# lab4.net
KiCad netlist of a schematic drawn in Altium Designer
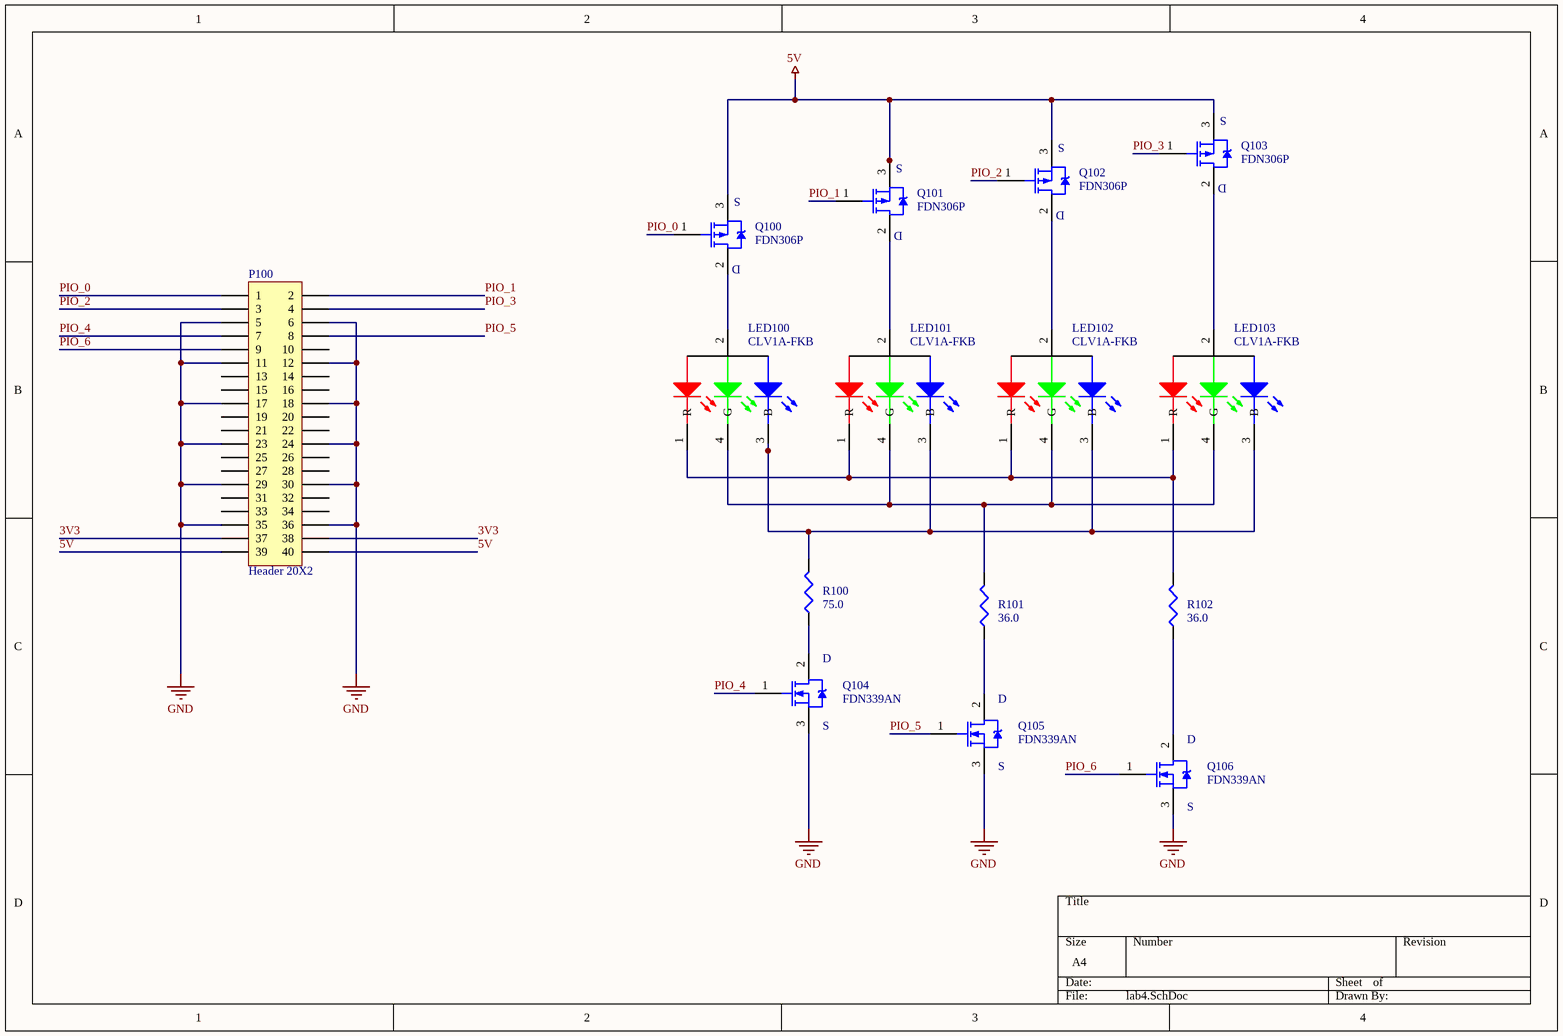
[diagram p0: lab4.SchDoc]

(export (version "E")
  (design (tool "Eeschema 10.0.6"))
  (components
    (comp (ref "LED100")
      (value "CLV1A-FKB")
      (footprint "PLCC4")
      (libsource (lib "My_LED") (part "CLV1A-FKB"))
    )
    (comp (ref "LED101")
      (value "CLV1A-FKB")
      (footprint "PLCC4")
      (libsource (lib "My_LED") (part "CLV1A-FKB"))
    )
    (comp (ref "LED102")
      (value "CLV1A-FKB")
      (footprint "PLCC4")
      (libsource (lib "My_LED") (part "CLV1A-FKB"))
    )
    (comp (ref "LED103")
      (value "CLV1A-FKB")
      (footprint "PLCC4")
      (libsource (lib "My_LED") (part "CLV1A-FKB"))
    )
    (comp (ref "P100")
      (value "Header 20X2")
      (footprint "HDR2X20")
      (description "Header, 20-Pin, Dual row")
      (fields (field (name "PUBLISHER") "Altium Limited"))
      (libsource (lib "Miscellaneous Connectors") (part "Header 20X2"))
    )
    (comp (ref "Q100")
      (value "FDN306P")
      (footprint "SOT23_M:SOT23-3M")
      (description "Pch MOSFET")
      (libsource (lib "MY_Fairchild_MOSFETS") (part "FDN304P"))
    )
    (comp (ref "Q101")
      (value "FDN306P")
      (footprint "SOT23_M:SOT23-3M")
      (description "Pch MOSFET")
      (libsource (lib "MY_Fairchild_MOSFETS") (part "FDN304P"))
    )
    (comp (ref "Q102")
      (value "FDN306P")
      (footprint "SOT23_M:SOT23-3M")
      (description "Pch MOSFET")
      (libsource (lib "MY_Fairchild_MOSFETS") (part "FDN304P"))
    )
    (comp (ref "Q103")
      (value "FDN306P")
      (footprint "SOT23_M:SOT23-3M")
      (description "Pch MOSFET")
      (libsource (lib "MY_Fairchild_MOSFETS") (part "FDN304P"))
    )
    (comp (ref "Q104")
      (value "FDN339AN")
      (footprint "SOT23_M:SOT23-3M")
      (description "Nch MOSFET")
      (libsource (lib "MY_Fairchild_MOSFETS") (part "FDN339AN"))
    )
    (comp (ref "Q105")
      (value "FDN339AN")
      (footprint "SOT23_M:SOT23-3M")
      (description "Nch MOSFET")
      (libsource (lib "MY_Fairchild_MOSFETS") (part "FDN339AN"))
    )
    (comp (ref "Q106")
      (value "FDN339AN")
      (footprint "SOT23_M:SOT23-3M")
      (description "Nch MOSFET")
      (libsource (lib "MY_Fairchild_MOSFETS") (part "FDN339AN"))
    )
    (comp (ref "R100")
      (value "75.0")
      (footprint "RESC2012M")
      (description "Resistor")
      (fields (field (name "Comment") "Res3") (field (name "PUBLISHER") "Altium Limited"))
      (libsource (lib "My_Miscellaneous Devices") (part "Res3"))
    )
    (comp (ref "R101")
      (value "36.0")
      (footprint "RESC2012M")
      (description "Resistor")
      (fields (field (name "Comment") "Res3") (field (name "PUBLISHER") "Altium Limited"))
      (libsource (lib "My_Miscellaneous Devices") (part "Res3"))
    )
    (comp (ref "R102")
      (value "36.0")
      (footprint "RESC2012M")
      (description "Resistor")
      (fields (field (name "Comment") "Res3") (field (name "PUBLISHER") "Altium Limited"))
      (libsource (lib "My_Miscellaneous Devices") (part "Res3"))
    )
  )
  (nets
    (net (code "1") (name "/3V3") (class "Default")
      (node (ref "P100") (pin "37") (pinfunction "37_37") (pintype "passive"))
      (node (ref "P100") (pin "38") (pinfunction "38_38") (pintype "passive"))
    )
    (net (code "2") (name "/PIO_0") (class "Default")
      (node (ref "P100") (pin "1") (pinfunction "1_1") (pintype "passive"))
      (node (ref "Q100") (pin "1") (pinfunction "G_1") (pintype "passive"))
    )
    (net (code "3") (name "/PIO_1") (class "Default")
      (node (ref "P100") (pin "2") (pinfunction "2_2") (pintype "passive"))
      (node (ref "Q101") (pin "1") (pinfunction "G_1") (pintype "passive"))
    )
    (net (code "4") (name "/PIO_2") (class "Default")
      (node (ref "P100") (pin "3") (pinfunction "3_3") (pintype "passive"))
      (node (ref "Q102") (pin "1") (pinfunction "G_1") (pintype "passive"))
    )
    (net (code "5") (name "/PIO_3") (class "Default")
      (node (ref "P100") (pin "4") (pinfunction "4_4") (pintype "passive"))
      (node (ref "Q103") (pin "1") (pinfunction "G_1") (pintype "passive"))
    )
    (net (code "6") (name "/PIO_4") (class "Default")
      (node (ref "P100") (pin "7") (pinfunction "7_7") (pintype "passive"))
      (node (ref "Q104") (pin "1") (pinfunction "G_1") (pintype "passive"))
    )
    (net (code "7") (name "/PIO_5") (class "Default")
      (node (ref "P100") (pin "8") (pinfunction "8_8") (pintype "passive"))
      (node (ref "Q105") (pin "1") (pinfunction "G_1") (pintype "passive"))
    )
    (net (code "8") (name "/PIO_6") (class "Default")
      (node (ref "P100") (pin "9") (pinfunction "9_9") (pintype "passive"))
      (node (ref "Q106") (pin "1") (pinfunction "G_1") (pintype "passive"))
    )
    (net (code "9") (name "5V") (class "Default")
      (node (ref "P100") (pin "39") (pinfunction "39_39") (pintype "passive"))
      (node (ref "P100") (pin "40") (pinfunction "40_40") (pintype "passive"))
      (node (ref "Q100") (pin "3") (pinfunction "S_3") (pintype "passive"))
      (node (ref "Q101") (pin "3") (pinfunction "S_3") (pintype "passive"))
      (node (ref "Q102") (pin "3") (pinfunction "S_3") (pintype "passive"))
      (node (ref "Q103") (pin "3") (pinfunction "S_3") (pintype "passive"))
    )
    (net (code "10") (name "GND") (class "Default")
      (node (ref "P100") (pin "11") (pinfunction "11_11") (pintype "passive"))
      (node (ref "P100") (pin "12") (pinfunction "12_12") (pintype "passive"))
      (node (ref "P100") (pin "17") (pinfunction "17_17") (pintype "passive"))
      (node (ref "P100") (pin "18") (pinfunction "18_18") (pintype "passive"))
      (node (ref "P100") (pin "23") (pinfunction "23_23") (pintype "passive"))
      (node (ref "P100") (pin "24") (pinfunction "24_24") (pintype "passive"))
      (node (ref "P100") (pin "29") (pinfunction "29_29") (pintype "passive"))
      (node (ref "P100") (pin "30") (pinfunction "30_30") (pintype "passive"))
      (node (ref "P100") (pin "35") (pinfunction "35_35") (pintype "passive"))
      (node (ref "P100") (pin "36") (pinfunction "36_36") (pintype "passive"))
      (node (ref "P100") (pin "5") (pinfunction "5_5") (pintype "passive"))
      (node (ref "P100") (pin "6") (pinfunction "6_6") (pintype "passive"))
      (node (ref "Q104") (pin "3") (pinfunction "S_3") (pintype "passive"))
      (node (ref "Q105") (pin "3") (pinfunction "S_3") (pintype "passive"))
      (node (ref "Q106") (pin "3") (pinfunction "S_3") (pintype "passive"))
    )
    (net (code "11") (name "Net-(LED100-A)") (class "Default")
      (node (ref "LED100") (pin "2") (pinfunction "A_2") (pintype "passive"))
      (node (ref "Q100") (pin "2") (pinfunction "D_2") (pintype "passive"))
    )
    (net (code "12") (name "Net-(LED100-B)") (class "Default")
      (node (ref "LED100") (pin "3") (pinfunction "B_3") (pintype "passive"))
      (node (ref "LED101") (pin "3") (pinfunction "B_3") (pintype "passive"))
      (node (ref "LED102") (pin "3") (pinfunction "B_3") (pintype "passive"))
      (node (ref "LED103") (pin "3") (pinfunction "B_3") (pintype "passive"))
      (node (ref "R100") (pin "2") (pinfunction "2_2") (pintype "passive"))
    )
    (net (code "13") (name "Net-(LED100-G)") (class "Default")
      (node (ref "LED100") (pin "4") (pinfunction "G_4") (pintype "passive"))
      (node (ref "LED101") (pin "4") (pinfunction "G_4") (pintype "passive"))
      (node (ref "LED102") (pin "4") (pinfunction "G_4") (pintype "passive"))
      (node (ref "LED103") (pin "4") (pinfunction "G_4") (pintype "passive"))
      (node (ref "R101") (pin "2") (pinfunction "2_2") (pintype "passive"))
    )
    (net (code "14") (name "Net-(LED100-R)") (class "Default")
      (node (ref "LED100") (pin "1") (pinfunction "R_1") (pintype "passive"))
      (node (ref "LED101") (pin "1") (pinfunction "R_1") (pintype "passive"))
      (node (ref "LED102") (pin "1") (pinfunction "R_1") (pintype "passive"))
      (node (ref "LED103") (pin "1") (pinfunction "R_1") (pintype "passive"))
      (node (ref "R102") (pin "2") (pinfunction "2_2") (pintype "passive"))
    )
    (net (code "15") (name "Net-(LED101-A)") (class "Default")
      (node (ref "LED101") (pin "2") (pinfunction "A_2") (pintype "passive"))
      (node (ref "Q101") (pin "2") (pinfunction "D_2") (pintype "passive"))
    )
    (net (code "16") (name "Net-(LED102-A)") (class "Default")
      (node (ref "LED102") (pin "2") (pinfunction "A_2") (pintype "passive"))
      (node (ref "Q102") (pin "2") (pinfunction "D_2") (pintype "passive"))
    )
    (net (code "17") (name "Net-(LED103-A)") (class "Default")
      (node (ref "LED103") (pin "2") (pinfunction "A_2") (pintype "passive"))
      (node (ref "Q103") (pin "2") (pinfunction "D_2") (pintype "passive"))
    )
    (net (code "18") (name "Net-(Q104-D)") (class "Default")
      (node (ref "Q104") (pin "2") (pinfunction "D_2") (pintype "passive"))
      (node (ref "R100") (pin "1") (pinfunction "1_1") (pintype "passive"))
    )
    (net (code "19") (name "Net-(Q105-D)") (class "Default")
      (node (ref "Q105") (pin "2") (pinfunction "D_2") (pintype "passive"))
      (node (ref "R101") (pin "1") (pinfunction "1_1") (pintype "passive"))
    )
    (net (code "20") (name "Net-(Q106-D)") (class "Default")
      (node (ref "Q106") (pin "2") (pinfunction "D_2") (pintype "passive"))
      (node (ref "R102") (pin "1") (pinfunction "1_1") (pintype "passive"))
    )
    (net (code "21") (name "unconnected-(P100-Pad10)") (class "Default")
      (node (ref "P100") (pin "10") (pinfunction "10_10") (pintype "passive"))
    )
    (net (code "22") (name "unconnected-(P100-Pad13)") (class "Default")
      (node (ref "P100") (pin "13") (pinfunction "13_13") (pintype "passive"))
    )
    (net (code "23") (name "unconnected-(P100-Pad14)") (class "Default")
      (node (ref "P100") (pin "14") (pinfunction "14_14") (pintype "passive"))
    )
    (net (code "24") (name "unconnected-(P100-Pad15)") (class "Default")
      (node (ref "P100") (pin "15") (pinfunction "15_15") (pintype "passive"))
    )
    (net (code "25") (name "unconnected-(P100-Pad16)") (class "Default")
      (node (ref "P100") (pin "16") (pinfunction "16_16") (pintype "passive"))
    )
    (net (code "26") (name "unconnected-(P100-Pad19)") (class "Default")
      (node (ref "P100") (pin "19") (pinfunction "19_19") (pintype "passive"))
    )
    (net (code "27") (name "unconnected-(P100-Pad20)") (class "Default")
      (node (ref "P100") (pin "20") (pinfunction "20_20") (pintype "passive"))
    )
    (net (code "28") (name "unconnected-(P100-Pad21)") (class "Default")
      (node (ref "P100") (pin "21") (pinfunction "21_21") (pintype "passive"))
    )
    (net (code "29") (name "unconnected-(P100-Pad22)") (class "Default")
      (node (ref "P100") (pin "22") (pinfunction "22_22") (pintype "passive"))
    )
    (net (code "30") (name "unconnected-(P100-Pad25)") (class "Default")
      (node (ref "P100") (pin "25") (pinfunction "25_25") (pintype "passive"))
    )
    (net (code "31") (name "unconnected-(P100-Pad26)") (class "Default")
      (node (ref "P100") (pin "26") (pinfunction "26_26") (pintype "passive"))
    )
    (net (code "32") (name "unconnected-(P100-Pad27)") (class "Default")
      (node (ref "P100") (pin "27") (pinfunction "27_27") (pintype "passive"))
    )
    (net (code "33") (name "unconnected-(P100-Pad28)") (class "Default")
      (node (ref "P100") (pin "28") (pinfunction "28_28") (pintype "passive"))
    )
    (net (code "34") (name "unconnected-(P100-Pad31)") (class "Default")
      (node (ref "P100") (pin "31") (pinfunction "31_31") (pintype "passive"))
    )
    (net (code "35") (name "unconnected-(P100-Pad32)") (class "Default")
      (node (ref "P100") (pin "32") (pinfunction "32_32") (pintype "passive"))
    )
    (net (code "36") (name "unconnected-(P100-Pad33)") (class "Default")
      (node (ref "P100") (pin "33") (pinfunction "33_33") (pintype "passive"))
    )
    (net (code "37") (name "unconnected-(P100-Pad34)") (class "Default")
      (node (ref "P100") (pin "34") (pinfunction "34_34") (pintype "passive"))
    )
  )
)
